# MainBoard_Top.net
KiCad netlist of a schematic drawn in Altium Designer
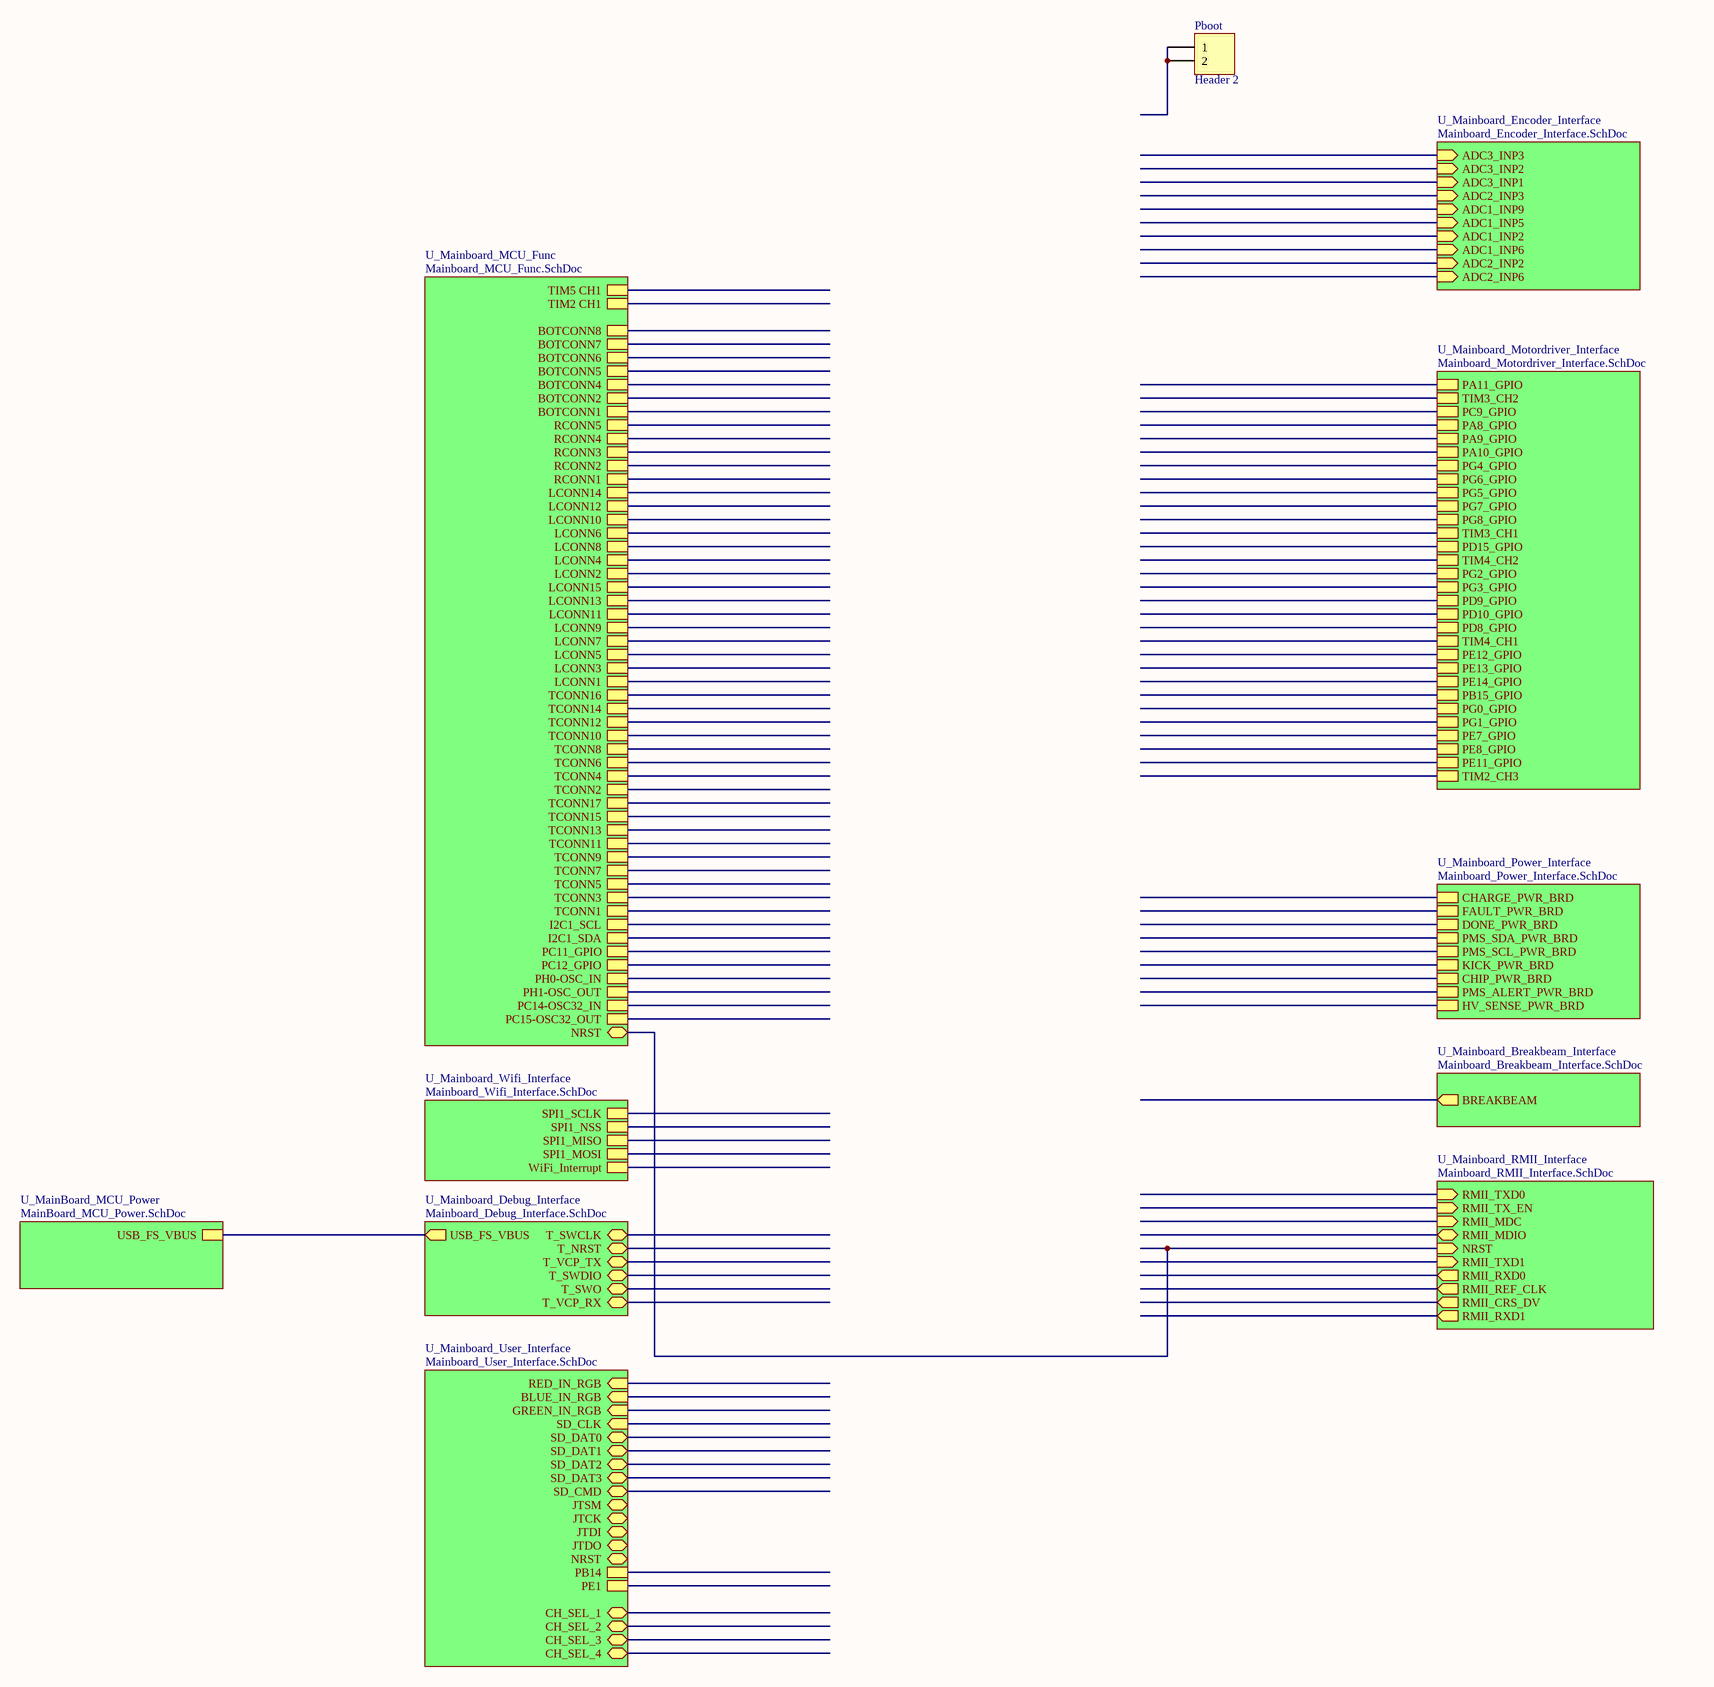
[diagram p0: MainBoard_Top.SchDoc]

(export (version "E")
  (design (tool "Eeschema 10.0.6"))
  (components
    (comp (ref "Pboot")
      (value "Header 2")
      (footprint "HDR1X2")
      (description "Header, 2-Pin")
      (fields (field (name "PUBLISHER") "Altium Limited"))
      (libsource (lib "Miscellaneous Connectors") (part "Header 2"))
    )
  )
  (nets
    (net (code "147") (name "Net-(Pboot-Pad1)") (class "Default")
      (node (ref "Pboot") (pin "1") (pinfunction "1_1") (pintype "passive"))
      (node (ref "Pboot") (pin "2") (pinfunction "2_2") (pintype "passive"))
    )
  )
)
